# Sheet1.net
KiCad netlist of a schematic drawn in Altium Designer
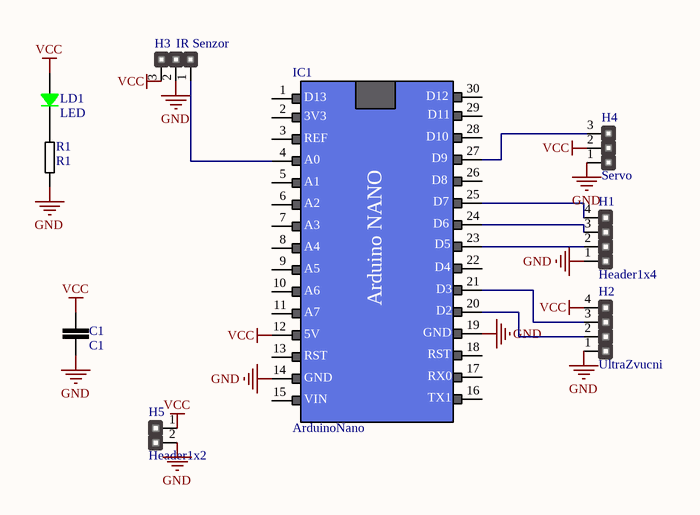
[diagram p0: Sheet1.SchDoc]

(export (version "E")
  (design (tool "Eeschema 10.0.6"))
  (components
    (comp (ref "C1") (value "C1") (footprint "C1(ceramic)") (libsource (lib "KILEX LIB SCH") (part "C1")))
    (comp (ref "H1")
      (value "Header1x4")
      (footprint "Header1x4")
      (libsource (lib "KILEX LIB SCH") (part "Header1x4"))
    )
    (comp (ref "H2")
      (value "UltraZvucni")
      (footprint "Header1x4")
      (libsource (lib "KILEX LIB SCH") (part "Header1x4"))
    )
    (comp (ref "H3")
      (value "IR Senzor")
      (footprint "Header 1x3")
      (libsource (lib "KILEX LIB SCH") (part "Header 1x3"))
    )
    (comp (ref "H4") (value "Servo") (footprint "Header 1x3") (libsource (lib "") (part "Header 1x3_1")))
    (comp (ref "H5")
      (value "Header1x2")
      (footprint "Header1x2")
      (libsource (lib "KILEX LIB SCH") (part "Header1x2"))
    )
    (comp (ref "IC1")
      (value "ArduinoNano")
      (footprint "Arduino Nano")
      (libsource (lib "KILEX LIB SCH") (part "ArduinoNano"))
    )
    (comp (ref "LD1") (value "LED") (footprint "LED SMD 3528") (libsource (lib "KILEX LIB SCH") (part "LED")))
    (comp (ref "R1") (value "R1") (footprint "R 0805") (libsource (lib "KILEX LIB SCH") (part "R1")))
  )
  (nets
    (net (code "1") (name "GND") (class "Default")
      (node (ref "C1") (pin "1") (pinfunction "1_1") (pintype "passive"))
      (node (ref "H1") (pin "1") (pinfunction "1_1") (pintype "passive"))
      (node (ref "H2") (pin "1") (pinfunction "1_1") (pintype "passive"))
      (node (ref "H3") (pin "2") (pinfunction "2_2") (pintype "passive"))
      (node (ref "H4") (pin "1") (pinfunction "1_1") (pintype "passive"))
      (node (ref "H5") (pin "2") (pinfunction "2_2") (pintype "passive"))
      (node (ref "IC1") (pin "14") (pinfunction "14_14") (pintype "passive"))
      (node (ref "IC1") (pin "19") (pinfunction "19_19") (pintype "passive"))
      (node (ref "R1") (pin "1") (pinfunction "1_1") (pintype "passive"))
    )
    (net (code "2") (name "Net-(H1-Pad2)") (class "Default")
      (node (ref "H1") (pin "2") (pinfunction "2_2") (pintype "passive"))
      (node (ref "IC1") (pin "23") (pinfunction "23_23") (pintype "passive"))
    )
    (net (code "3") (name "Net-(H1-Pad3)") (class "Default")
      (node (ref "H1") (pin "3") (pinfunction "3_3") (pintype "passive"))
      (node (ref "IC1") (pin "24") (pinfunction "24_24") (pintype "passive"))
    )
    (net (code "4") (name "Net-(H1-Pad4)") (class "Default")
      (node (ref "H1") (pin "4") (pinfunction "4_4") (pintype "passive"))
      (node (ref "IC1") (pin "25") (pinfunction "25_25") (pintype "passive"))
    )
    (net (code "5") (name "Net-(H2-Pad2)") (class "Default")
      (node (ref "H2") (pin "2") (pinfunction "2_2") (pintype "passive"))
      (node (ref "IC1") (pin "20") (pinfunction "20_20") (pintype "passive"))
    )
    (net (code "6") (name "Net-(H2-Pad3)") (class "Default")
      (node (ref "H2") (pin "3") (pinfunction "3_3") (pintype "passive"))
      (node (ref "IC1") (pin "21") (pinfunction "21_21") (pintype "passive"))
    )
    (net (code "7") (name "Net-(H3-Pad1)") (class "Default")
      (node (ref "H3") (pin "1") (pinfunction "1_1") (pintype "passive"))
      (node (ref "IC1") (pin "4") (pinfunction "4_4") (pintype "passive"))
    )
    (net (code "8") (name "Net-(H4-Pad3)") (class "Default")
      (node (ref "H4") (pin "3") (pinfunction "3_3") (pintype "passive"))
      (node (ref "IC1") (pin "27") (pinfunction "27_27") (pintype "passive"))
    )
    (net (code "9") (name "Net-(LD1-Pad2)") (class "Default")
      (node (ref "LD1") (pin "2") (pinfunction "2_2") (pintype "passive"))
      (node (ref "R1") (pin "2") (pinfunction "2_2") (pintype "passive"))
    )
    (net (code "10") (name "VCC") (class "Default")
      (node (ref "C1") (pin "2") (pinfunction "2_2") (pintype "passive"))
      (node (ref "H2") (pin "4") (pinfunction "4_4") (pintype "passive"))
      (node (ref "H3") (pin "3") (pinfunction "3_3") (pintype "passive"))
      (node (ref "H4") (pin "2") (pinfunction "2_2") (pintype "passive"))
      (node (ref "H5") (pin "1") (pinfunction "1_1") (pintype "passive"))
      (node (ref "IC1") (pin "12") (pinfunction "12_12") (pintype "passive"))
      (node (ref "LD1") (pin "1") (pinfunction "1_1") (pintype "passive"))
    )
    (net (code "11") (name "unconnected-(IC1-Pad1)") (class "Default")
      (node (ref "IC1") (pin "1") (pinfunction "1_1") (pintype "passive"))
    )
    (net (code "12") (name "unconnected-(IC1-Pad2)") (class "Default")
      (node (ref "IC1") (pin "2") (pinfunction "2_2") (pintype "passive"))
    )
    (net (code "13") (name "unconnected-(IC1-Pad3)") (class "Default")
      (node (ref "IC1") (pin "3") (pinfunction "3_3") (pintype "passive"))
    )
    (net (code "14") (name "unconnected-(IC1-Pad5)") (class "Default")
      (node (ref "IC1") (pin "5") (pinfunction "5_5") (pintype "passive"))
    )
    (net (code "15") (name "unconnected-(IC1-Pad6)") (class "Default")
      (node (ref "IC1") (pin "6") (pinfunction "6_6") (pintype "passive"))
    )
    (net (code "16") (name "unconnected-(IC1-Pad7)") (class "Default")
      (node (ref "IC1") (pin "7") (pinfunction "7_7") (pintype "passive"))
    )
    (net (code "17") (name "unconnected-(IC1-Pad8)") (class "Default")
      (node (ref "IC1") (pin "8") (pinfunction "8_8") (pintype "passive"))
    )
    (net (code "18") (name "unconnected-(IC1-Pad9)") (class "Default")
      (node (ref "IC1") (pin "9") (pinfunction "9_9") (pintype "passive"))
    )
    (net (code "19") (name "unconnected-(IC1-Pad10)") (class "Default")
      (node (ref "IC1") (pin "10") (pinfunction "10_10") (pintype "passive"))
    )
    (net (code "20") (name "unconnected-(IC1-Pad11)") (class "Default")
      (node (ref "IC1") (pin "11") (pinfunction "11_11") (pintype "passive"))
    )
    (net (code "21") (name "unconnected-(IC1-Pad13)") (class "Default")
      (node (ref "IC1") (pin "13") (pinfunction "13_13") (pintype "passive"))
    )
    (net (code "22") (name "unconnected-(IC1-Pad15)") (class "Default")
      (node (ref "IC1") (pin "15") (pinfunction "15_15") (pintype "passive"))
    )
    (net (code "23") (name "unconnected-(IC1-Pad16)") (class "Default")
      (node (ref "IC1") (pin "16") (pinfunction "16_16") (pintype "passive"))
    )
    (net (code "24") (name "unconnected-(IC1-Pad17)") (class "Default")
      (node (ref "IC1") (pin "17") (pinfunction "17_17") (pintype "passive"))
    )
    (net (code "25") (name "unconnected-(IC1-Pad18)") (class "Default")
      (node (ref "IC1") (pin "18") (pinfunction "18_18") (pintype "passive"))
    )
    (net (code "26") (name "unconnected-(IC1-Pad22)") (class "Default")
      (node (ref "IC1") (pin "22") (pinfunction "22_22") (pintype "passive"))
    )
    (net (code "27") (name "unconnected-(IC1-Pad26)") (class "Default")
      (node (ref "IC1") (pin "26") (pinfunction "26_26") (pintype "passive"))
    )
    (net (code "28") (name "unconnected-(IC1-Pad28)") (class "Default")
      (node (ref "IC1") (pin "28") (pinfunction "28_28") (pintype "passive"))
    )
    (net (code "29") (name "unconnected-(IC1-Pad29)") (class "Default")
      (node (ref "IC1") (pin "29") (pinfunction "29_29") (pintype "passive"))
    )
    (net (code "30") (name "unconnected-(IC1-Pad30)") (class "Default")
      (node (ref "IC1") (pin "30") (pinfunction "30_30") (pintype "passive"))
    )
  )
)
